# power.net
KiCad netlist of a schematic drawn in Altium Designer
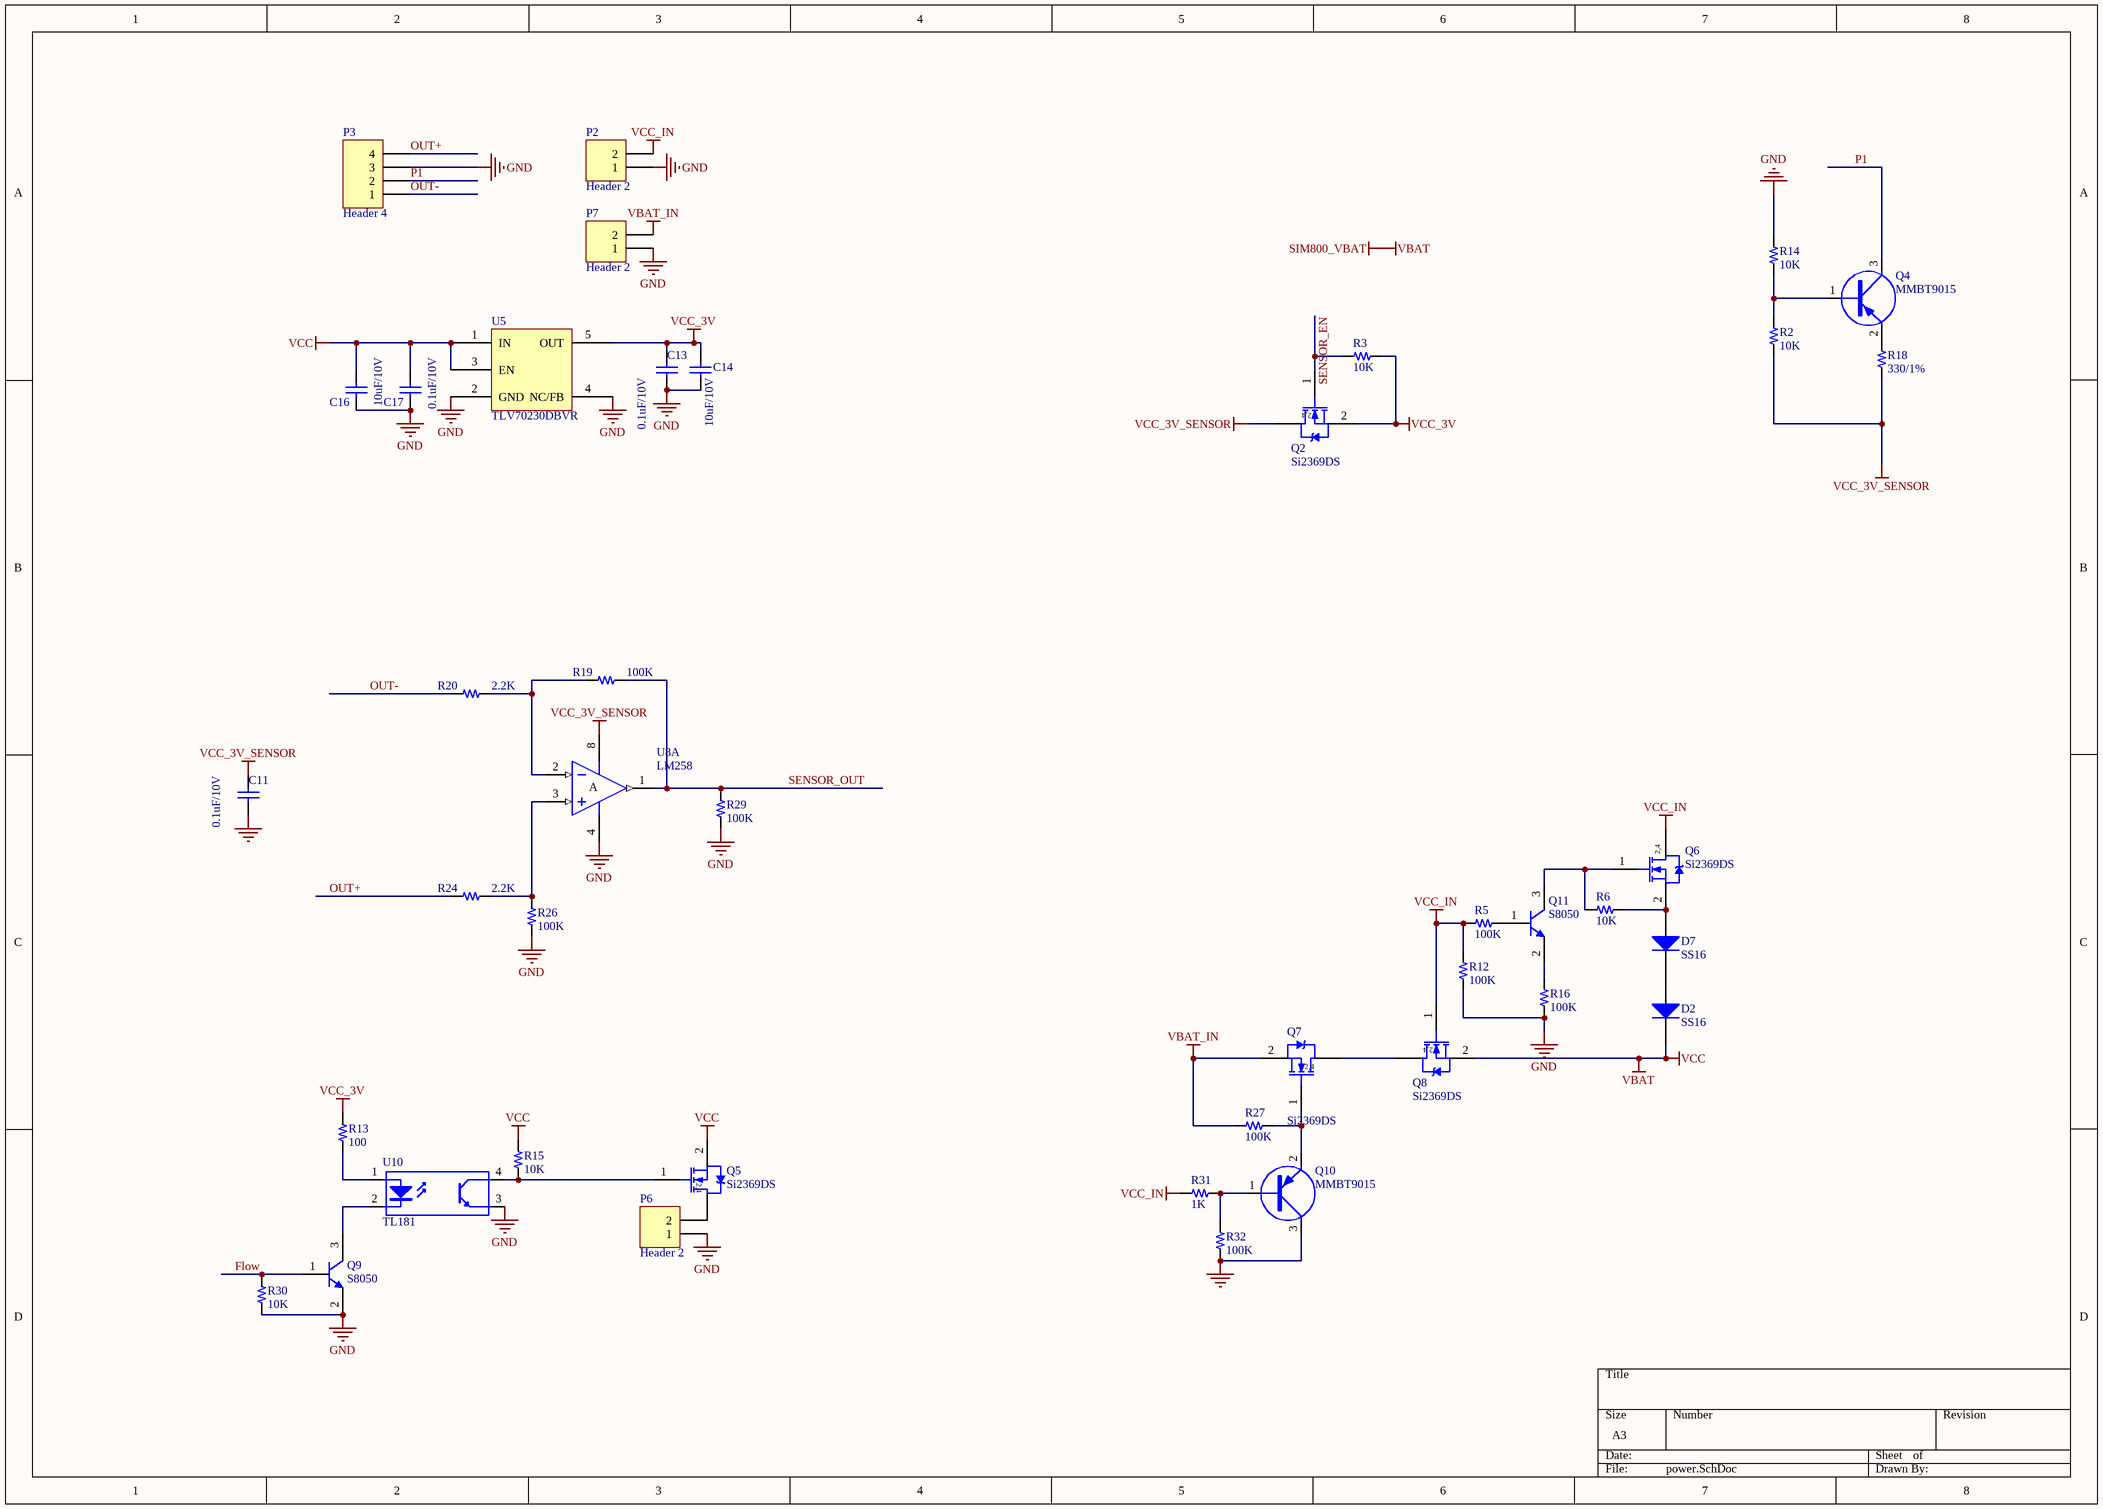
[diagram p0: power.SchDoc]

(export (version "E")
  (design (tool "Eeschema 10.0.6"))
  (components
    (comp (ref "C11")
      (value "0.1uF/10V")
      (footprint "0603C")
      (description "Capacitor")
      (fields (field (name "PUBLISHER") "Altium Limited"))
      (libsource (lib "Miscellaneous Devices") (part "Cap"))
    )
    (comp (ref "C13")
      (value "0.1uF/10V")
      (footprint "0603C")
      (description "Capacitor")
      (fields (field (name "PUBLISHER") "Altium Limited"))
      (libsource (lib "Miscellaneous Devices") (part "Cap"))
    )
    (comp (ref "C14")
      (value "10uF/10V")
      (footprint "0603C")
      (description "Capacitor")
      (fields (field (name "PUBLISHER") "Altium Limited"))
      (libsource (lib "Miscellaneous Devices") (part "Cap"))
    )
    (comp (ref "C16")
      (value "10uF/10V")
      (footprint "0603C")
      (description "Capacitor")
      (fields (field (name "PUBLISHER") "Altium Limited"))
      (libsource (lib "Miscellaneous Devices") (part "Cap"))
    )
    (comp (ref "C17")
      (value "0.1uF/10V")
      (footprint "0603C")
      (description "Capacitor")
      (fields (field (name "PUBLISHER") "Altium Limited"))
      (libsource (lib "Miscellaneous Devices") (part "Cap"))
    )
    (comp (ref "D2")
      (value "SS16")
      (footprint "SMA")
      (description "High Conductance Fast Diode")
      (fields (field (name "PUBLISHER") "Altium Limited"))
      (libsource (lib "Miscellaneous Devices") (part "Diode 1N4148"))
    )
    (comp (ref "D7")
      (value "SS16")
      (footprint "SMA")
      (description "High Conductance Fast Diode")
      (fields (field (name "PUBLISHER") "Altium Limited"))
      (libsource (lib "Miscellaneous Devices") (part "Diode 1N4148"))
    )
    (comp (ref "P2")
      (value "Header 2")
      (footprint "2X2.54MM")
      (description "Header, 2-Pin")
      (fields (field (name "PUBLISHER") "Altium Limited"))
      (libsource (lib "Miscellaneous Connectors") (part "Header 2"))
    )
    (comp (ref "P3")
      (value "Header 4")
      (footprint "HDR1X4")
      (description "Header, 4-Pin")
      (fields (field (name "PUBLISHER") "Altium Limited"))
      (libsource (lib "Miscellaneous Connectors") (part "Header 4"))
    )
    (comp (ref "P6")
      (value "Header 2")
      (footprint "HDR1X2")
      (description "Header, 2-Pin")
      (fields (field (name "PUBLISHER") "Altium Limited"))
      (libsource (lib "Miscellaneous Connectors") (part "Header 2"))
    )
    (comp (ref "P7")
      (value "Header 2")
      (footprint "2X2.54MM")
      (description "Header, 2-Pin")
      (fields (field (name "PUBLISHER") "Altium Limited"))
      (libsource (lib "Miscellaneous Connectors") (part "Header 2"))
    )
    (comp (ref "Q2")
      (value "Si2369DS")
      (footprint "SOT23-3")
      (description "BUK92150-55A")
      (fields (field (name "PUBLISHER") "Altium Limited"))
      (libsource (lib "Schlib1") (part "BUK92150-55A"))
    )
    (comp (ref "Q4") (value "MMBT9015") (footprint "SOT23-3") (libsource (lib "Schlib1") (part "PNP")))
    (comp (ref "Q5")
      (value "Si2369DS")
      (footprint "SOT23-3")
      (description "BUK92150-55A")
      (fields (field (name "PUBLISHER") "Altium Limited"))
      (libsource (lib "") (part "BUK92150-55A_1"))
    )
    (comp (ref "Q6")
      (value "Si2369DS")
      (footprint "SOT23-3")
      (description "BUK92150-55A")
      (fields (field (name "PUBLISHER") "Altium Limited"))
      (libsource (lib "") (part "BUK92150-55A_1"))
    )
    (comp (ref "Q7")
      (value "Si2369DS")
      (footprint "SOT23-3")
      (description "BUK92150-55A")
      (fields (field (name "PUBLISHER") "Altium Limited"))
      (libsource (lib "Schlib1") (part "BUK92150-55A"))
    )
    (comp (ref "Q8")
      (value "Si2369DS")
      (footprint "SOT23-3")
      (description "BUK92150-55A")
      (fields (field (name "PUBLISHER") "Altium Limited"))
      (libsource (lib "Schlib1") (part "BUK92150-55A"))
    )
    (comp (ref "Q9") (value "S8050") (footprint "SOT23-3") (libsource (lib "Schlib1") (part "NPN")))
    (comp (ref "Q10") (value "MMBT9015") (footprint "SOT23-3") (libsource (lib "Schlib1") (part "PNP")))
    (comp (ref "Q11") (value "S8050") (footprint "SOT23-3") (libsource (lib "Schlib1") (part "NPN")))
    (comp (ref "R2") (value "10K") (footprint "0603R") (description "R") (libsource (lib "JRJ_1") (part "R")))
    (comp (ref "R3") (value "10K") (footprint "0603R") (description "R") (libsource (lib "JRJ_1") (part "R")))
    (comp (ref "R5")
      (value "100K")
      (footprint "0603R")
      (description "R")
      (libsource (lib "JRJ_1") (part "R"))
    )
    (comp (ref "R6") (value "10K") (footprint "0603R") (description "R") (libsource (lib "JRJ_1") (part "R")))
    (comp (ref "R12")
      (value "100K")
      (footprint "0603R")
      (description "R")
      (libsource (lib "JRJ_1") (part "R"))
    )
    (comp (ref "R13")
      (value "100")
      (footprint "0603R")
      (description "R")
      (libsource (lib "JRJ_1") (part "R"))
    )
    (comp (ref "R14")
      (value "10K")
      (footprint "0603R")
      (description "R")
      (libsource (lib "JRJ_1") (part "R"))
    )
    (comp (ref "R15")
      (value "10K")
      (footprint "0603R")
      (description "R")
      (libsource (lib "JRJ_1") (part "R"))
    )
    (comp (ref "R16")
      (value "100K")
      (footprint "0603R")
      (description "R")
      (libsource (lib "JRJ_1") (part "R"))
    )
    (comp (ref "R18")
      (value "330/1%")
      (footprint "0603R")
      (description "R")
      (libsource (lib "JRJ_1") (part "R"))
    )
    (comp (ref "R19")
      (value "100K")
      (footprint "0603R")
      (description "R")
      (libsource (lib "JRJ_1") (part "R"))
    )
    (comp (ref "R20")
      (value "2.2K")
      (footprint "0603R")
      (description "R")
      (libsource (lib "JRJ_1") (part "R"))
    )
    (comp (ref "R24")
      (value "2.2K")
      (footprint "0603R")
      (description "R")
      (libsource (lib "JRJ_1") (part "R"))
    )
    (comp (ref "R26")
      (value "100K")
      (footprint "0603R")
      (description "R")
      (libsource (lib "JRJ_1") (part "R"))
    )
    (comp (ref "R27")
      (value "100K")
      (footprint "0603R")
      (description "R")
      (libsource (lib "JRJ_1") (part "R"))
    )
    (comp (ref "R29")
      (value "100K")
      (footprint "0603R")
      (description "R")
      (libsource (lib "JRJ_1") (part "R"))
    )
    (comp (ref "R30")
      (value "10K")
      (footprint "0603R")
      (description "R")
      (libsource (lib "JRJ_1") (part "R"))
    )
    (comp (ref "R31") (value "1K") (footprint "0603R") (description "R") (libsource (lib "JRJ_1") (part "R")))
    (comp (ref "R32")
      (value "100K")
      (footprint "0603R")
      (description "R")
      (libsource (lib "JRJ_1") (part "R"))
    )
    (comp (ref "U5")
      (value "TLV70230DBVR")
      (footprint "SOT23-5(DBV)")
      (libsource (lib "Schlib_20110825") (part "TLV70230DBVR"))
    )
    (comp (ref "U8") (value "LM258") (footprint "so-8") (libsource (lib "Schlib_20110825") (part "LM258")))
    (comp (ref "U10")
      (value "TL181")
      (footprint "DIP-4")
      (description "4-Pin Phototransistor Optocoupler")
      (fields (field (name "PUBLISHER") "Altium Limited"))
      (libsource (lib "Miscellaneous Devices") (part "Optoisolator1"))
    )
  )
  (nets
    (net (code "1") (name "/Flow") (class "Default")
      (node (ref "Q9") (pin "1") (pinfunction "B_1") (pintype "passive"))
      (node (ref "R30") (pin "2") (pintype "passive"))
    )
    (net (code "2") (name "/OUT+") (class "Default")
      (node (ref "P3") (pin "4") (pinfunction "4_4") (pintype "passive"))
      (node (ref "R24") (pin "1") (pintype "passive"))
    )
    (net (code "3") (name "/OUT-") (class "Default")
      (node (ref "P3") (pin "1") (pinfunction "1_1") (pintype "passive"))
      (node (ref "R20") (pin "1") (pintype "passive"))
    )
    (net (code "4") (name "/P1") (class "Default")
      (node (ref "P3") (pin "2") (pinfunction "2_2") (pintype "passive"))
      (node (ref "Q4") (pin "3") (pinfunction "C_3") (pintype "passive"))
    )
    (net (code "5") (name "/SENSOR_EN") (class "Default")
      (node (ref "Q2") (pin "1") (pinfunction "G_1") (pintype "passive"))
      (node (ref "R3") (pin "2") (pintype "passive"))
    )
    (net (code "6") (name "/SENSOR_OUT") (class "Default")
      (node (ref "R19") (pin "2") (pintype "passive"))
      (node (ref "R29") (pin "2") (pintype "passive"))
      (node (ref "U8") (pin "1") (pinfunction "OUT_1") (pintype "output"))
    )
    (net (code "7") (name "GND") (class "Default")
      (node (ref "C11") (pin "2") (pinfunction "2_2") (pintype "passive"))
      (node (ref "C13") (pin "2") (pinfunction "2_2") (pintype "passive"))
      (node (ref "C14") (pin "1") (pinfunction "1_1") (pintype "passive"))
      (node (ref "C16") (pin "1") (pinfunction "1_1") (pintype "passive"))
      (node (ref "C17") (pin "2") (pinfunction "2_2") (pintype "passive"))
      (node (ref "P2") (pin "1") (pinfunction "1_1") (pintype "passive"))
      (node (ref "P3") (pin "3") (pinfunction "3_3") (pintype "passive"))
      (node (ref "P6") (pin "1") (pinfunction "1_1") (pintype "passive"))
      (node (ref "P7") (pin "1") (pinfunction "1_1") (pintype "passive"))
      (node (ref "Q10") (pin "3") (pinfunction "C_3") (pintype "passive"))
      (node (ref "Q9") (pin "2") (pinfunction "E_2") (pintype "passive"))
      (node (ref "R12") (pin "2") (pintype "passive"))
      (node (ref "R14") (pin "2") (pintype "passive"))
      (node (ref "R16") (pin "1") (pintype "passive"))
      (node (ref "R26") (pin "1") (pintype "passive"))
      (node (ref "R29") (pin "1") (pintype "passive"))
      (node (ref "R30") (pin "1") (pintype "passive"))
      (node (ref "R32") (pin "1") (pintype "passive"))
      (node (ref "U10") (pin "3") (pinfunction "E_3") (pintype "passive"))
      (node (ref "U5") (pin "2") (pinfunction "GND_2") (pintype "passive"))
      (node (ref "U5") (pin "4") (pinfunction "NC/FB_4") (pintype "passive"))
      (node (ref "U8") (pin "4") (pinfunction "V-_4") (pintype "power_in"))
    )
    (net (code "8") (name "Net-(D2-A)") (class "Default")
      (node (ref "D2") (pin "1") (pinfunction "A_1") (pintype "passive"))
      (node (ref "D7") (pin "2") (pinfunction "K_2") (pintype "passive"))
    )
    (net (code "9") (name "Net-(D7-A)") (class "Default")
      (node (ref "D7") (pin "1") (pinfunction "A_1") (pintype "passive"))
      (node (ref "Q6") (pin "2") (pinfunction "S_2") (pintype "passive"))
      (node (ref "R6") (pin "1") (pintype "passive"))
    )
    (net (code "10") (name "Net-(Q4-B)") (class "Default")
      (node (ref "Q4") (pin "1") (pinfunction "B_1") (pintype "passive"))
      (node (ref "R14") (pin "1") (pintype "passive"))
      (node (ref "R2") (pin "2") (pintype "passive"))
    )
    (net (code "11") (name "Net-(Q4-E)") (class "Default")
      (node (ref "Q4") (pin "2") (pinfunction "E_2") (pintype "passive"))
      (node (ref "R18") (pin "2") (pintype "passive"))
    )
    (net (code "12") (name "Net-(Q5-D)") (class "Default")
      (node (ref "P6") (pin "2") (pinfunction "2_2") (pintype "passive"))
      (node (ref "Q5") (pin "3") (pinfunction "D_3") (pintype "passive"))
    )
    (net (code "13") (name "Net-(Q5-G)") (class "Default")
      (node (ref "Q5") (pin "1") (pinfunction "G_1") (pintype "passive"))
      (node (ref "R15") (pin "1") (pintype "passive"))
      (node (ref "U10") (pin "4") (pinfunction "C_4") (pintype "passive"))
    )
    (net (code "14") (name "Net-(Q7-D)") (class "Default")
      (node (ref "Q7") (pin "3") (pinfunction "D_3") (pintype "passive"))
      (node (ref "Q8") (pin "3") (pinfunction "D_3") (pintype "passive"))
    )
    (net (code "15") (name "Net-(Q9-C)") (class "Default")
      (node (ref "Q9") (pin "3") (pinfunction "C_3") (pintype "passive"))
      (node (ref "U10") (pin "2") (pinfunction "K_2") (pintype "passive"))
    )
    (net (code "16") (name "Net-(Q10-B)") (class "Default")
      (node (ref "Q10") (pin "1") (pinfunction "B_1") (pintype "passive"))
      (node (ref "R31") (pin "2") (pintype "passive"))
      (node (ref "R32") (pin "2") (pintype "passive"))
    )
    (net (code "17") (name "Net-(Q10-E)") (class "Default")
      (node (ref "Q10") (pin "2") (pinfunction "E_2") (pintype "passive"))
      (node (ref "Q7") (pin "1") (pinfunction "G_1") (pintype "passive"))
      (node (ref "R27") (pin "2") (pintype "passive"))
    )
    (net (code "18") (name "Net-(Q11-B)") (class "Default")
      (node (ref "Q11") (pin "1") (pinfunction "B_1") (pintype "passive"))
      (node (ref "R5") (pin "2") (pintype "passive"))
    )
    (net (code "19") (name "Net-(Q11-C)") (class "Default")
      (node (ref "Q11") (pin "3") (pinfunction "C_3") (pintype "passive"))
      (node (ref "Q6") (pin "1") (pinfunction "G_1") (pintype "passive"))
      (node (ref "R6") (pin "2") (pintype "passive"))
    )
    (net (code "20") (name "Net-(Q11-E)") (class "Default")
      (node (ref "Q11") (pin "2") (pinfunction "E_2") (pintype "passive"))
      (node (ref "R16") (pin "2") (pintype "passive"))
    )
    (net (code "21") (name "Net-(U8A-IN+)") (class "Default")
      (node (ref "R24") (pin "2") (pintype "passive"))
      (node (ref "R26") (pin "2") (pintype "passive"))
      (node (ref "U8") (pin "3") (pinfunction "IN+_3") (pintype "input"))
    )
    (net (code "22") (name "Net-(U8A-IN-)") (class "Default")
      (node (ref "R19") (pin "1") (pintype "passive"))
      (node (ref "R20") (pin "2") (pintype "passive"))
      (node (ref "U8") (pin "2") (pinfunction "IN-_2") (pintype "input"))
    )
    (net (code "23") (name "Net-(U10-A)") (class "Default")
      (node (ref "R13") (pin "1") (pintype "passive"))
      (node (ref "U10") (pin "1") (pinfunction "A_1") (pintype "passive"))
    )
    (net (code "24") (name "SIM800_VBAT") (class "Default")
      (node (ref "C16") (pin "2") (pinfunction "2_2") (pintype "passive"))
      (node (ref "C17") (pin "1") (pinfunction "1_1") (pintype "passive"))
      (node (ref "D2") (pin "2") (pinfunction "K_2") (pintype "passive"))
      (node (ref "Q5") (pin "2") (pinfunction "S_2") (pintype "passive"))
      (node (ref "Q8") (pin "2") (pinfunction "S_2") (pintype "passive"))
      (node (ref "R15") (pin "2") (pintype "passive"))
      (node (ref "U5") (pin "1") (pinfunction "IN_1") (pintype "passive"))
      (node (ref "U5") (pin "3") (pinfunction "EN_3") (pintype "passive"))
    )
    (net (code "25") (name "VBAT_IN") (class "Default")
      (node (ref "P7") (pin "2") (pinfunction "2_2") (pintype "passive"))
      (node (ref "Q7") (pin "2") (pinfunction "S_2") (pintype "passive"))
      (node (ref "R27") (pin "1") (pintype "passive"))
    )
    (net (code "26") (name "VCC_3V") (class "Default")
      (node (ref "C13") (pin "1") (pinfunction "1_1") (pintype "passive"))
      (node (ref "C14") (pin "2") (pinfunction "2_2") (pintype "passive"))
      (node (ref "Q2") (pin "2") (pinfunction "S_2") (pintype "passive"))
      (node (ref "R13") (pin "2") (pintype "passive"))
      (node (ref "R3") (pin "1") (pintype "passive"))
      (node (ref "U5") (pin "5") (pinfunction "OUT_5") (pintype "passive"))
    )
    (net (code "27") (name "VCC_3V_SENSOR") (class "Default")
      (node (ref "C11") (pin "1") (pinfunction "1_1") (pintype "passive"))
      (node (ref "Q2") (pin "3") (pinfunction "D_3") (pintype "passive"))
      (node (ref "R18") (pin "1") (pintype "passive"))
      (node (ref "R2") (pin "1") (pintype "passive"))
      (node (ref "U8") (pin "8") (pinfunction "V+_8") (pintype "power_in"))
    )
    (net (code "28") (name "VCC_IN") (class "Default")
      (node (ref "P2") (pin "2") (pinfunction "2_2") (pintype "passive"))
      (node (ref "Q6") (pin "3") (pinfunction "D_3") (pintype "passive"))
      (node (ref "Q8") (pin "1") (pinfunction "G_1") (pintype "passive"))
      (node (ref "R12") (pin "1") (pintype "passive"))
      (node (ref "R31") (pin "1") (pintype "passive"))
      (node (ref "R5") (pin "1") (pintype "passive"))
    )
  )
)
